# diode_sampling_gate_xformer.net
KiCad netlist of a schematic drawn in EAGLE
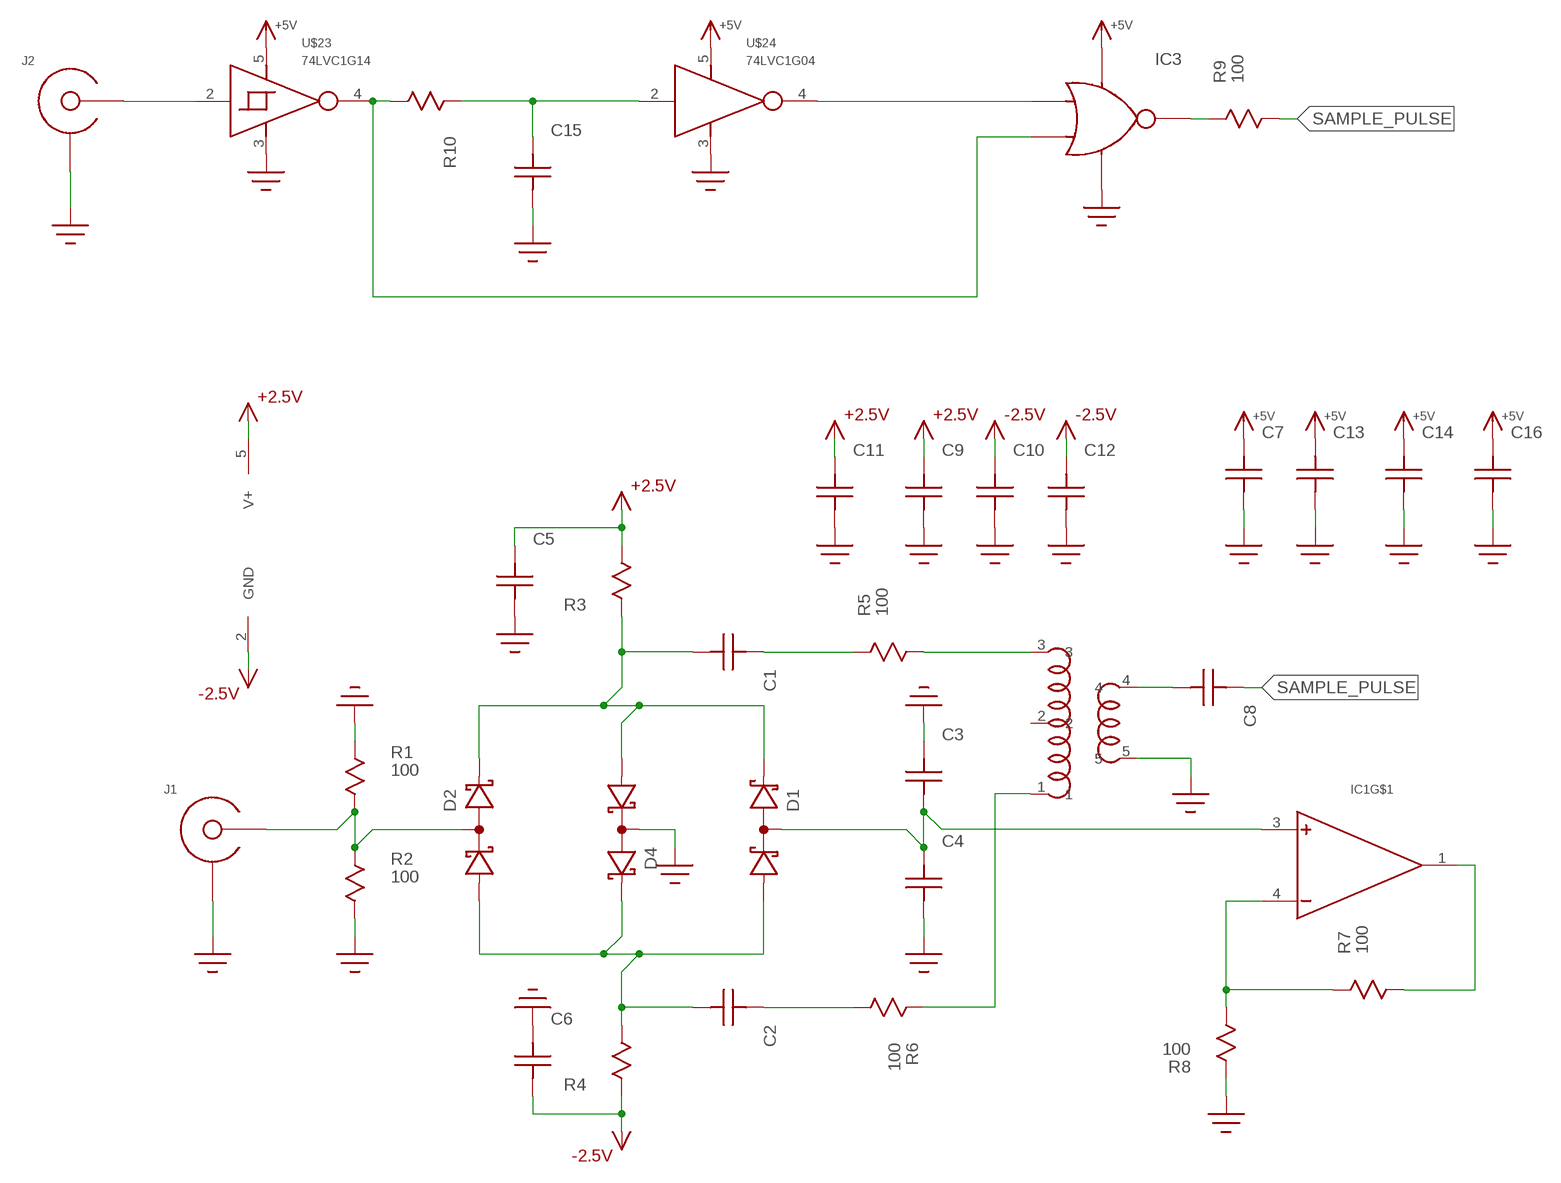
[diagram p0: schematic, sheet 1]

(export (version "E")
  (design (tool "Eeschema 10.0.6"))
  (components
    (comp (ref "C1")
      (value "C0603")
      (footprint "eagle-import:C0603")
      (libsource (lib "eagle-import") (part "C0603"))
    )
    (comp (ref "C2")
      (value "C0603")
      (footprint "eagle-import:C0603")
      (libsource (lib "eagle-import") (part "C0603"))
    )
    (comp (ref "C3")
      (value "C0603")
      (footprint "eagle-import:C0603")
      (libsource (lib "eagle-import") (part "C0603"))
    )
    (comp (ref "C4")
      (value "C0603")
      (footprint "eagle-import:C0603")
      (libsource (lib "eagle-import") (part "C0603"))
    )
    (comp (ref "C5")
      (value "C0603")
      (footprint "eagle-import:C0603")
      (libsource (lib "eagle-import") (part "C0603"))
    )
    (comp (ref "C6")
      (value "C0603")
      (footprint "eagle-import:C0603")
      (libsource (lib "eagle-import") (part "C0603"))
    )
    (comp (ref "C7")
      (value "C0603")
      (footprint "eagle-import:C0603")
      (libsource (lib "eagle-import") (part "C0603"))
    )
    (comp (ref "C8")
      (value "C0603")
      (footprint "eagle-import:C0603")
      (libsource (lib "eagle-import") (part "C0603"))
    )
    (comp (ref "C9")
      (value "C0603")
      (footprint "eagle-import:C0603")
      (libsource (lib "eagle-import") (part "C0603"))
    )
    (comp (ref "C10")
      (value "C0603")
      (footprint "eagle-import:C0603")
      (libsource (lib "eagle-import") (part "C0603"))
    )
    (comp (ref "C11")
      (value "C0805")
      (footprint "eagle-import:0805")
      (libsource (lib "eagle-import") (part "C0805"))
    )
    (comp (ref "C12")
      (value "C0805")
      (footprint "eagle-import:0805")
      (libsource (lib "eagle-import") (part "C0805"))
    )
    (comp (ref "C13")
      (value "C0603")
      (footprint "eagle-import:C0603")
      (libsource (lib "eagle-import") (part "C0603"))
    )
    (comp (ref "C14")
      (value "C0603")
      (footprint "eagle-import:C0603")
      (libsource (lib "eagle-import") (part "C0603"))
    )
    (comp (ref "C15")
      (value "C0603")
      (footprint "eagle-import:C0603")
      (libsource (lib "eagle-import") (part "C0603"))
    )
    (comp (ref "C16")
      (value "C0805")
      (footprint "eagle-import:0805")
      (libsource (lib "eagle-import") (part "C0805"))
    )
    (comp (ref "D1")
      (value "BAS40-04")
      (footprint "eagle-import:SOT-23")
      (libsource (lib "eagle-import") (part "BAS40-04"))
    )
    (comp (ref "D2")
      (value "BAS40-04")
      (footprint "eagle-import:SOT-23")
      (libsource (lib "eagle-import") (part "BAS40-04"))
    )
    (comp (ref "D4")
      (value "BAS40-04")
      (footprint "eagle-import:SOT-23")
      (libsource (lib "eagle-import") (part "BAS40-04"))
    )
    (comp (ref "IC1")
      (value "MCP6V81")
      (footprint "eagle-import:SOT23-5")
      (libsource (lib "eagle-import") (part "MCP6V81"))
    )
    (comp (ref "IC3")
      (value "74LVC1G02")
      (footprint "eagle-import:SOT23-5")
      (libsource (lib "eagle-import") (part "74LVC1G02"))
    )
    (comp (ref "J1")
      (value "EDGE_LAUNCH_JACK")
      (footprint "eagle-import:EDGE_LAUNCH_RF_CON")
      (libsource (lib "eagle-import") (part "EDGE_LAUNCH_JACK"))
    )
    (comp (ref "J2")
      (value "EDGE_LAUNCH_JACK")
      (footprint "eagle-import:EDGE_LAUNCH_RF_CON")
      (libsource (lib "eagle-import") (part "EDGE_LAUNCH_JACK"))
    )
    (comp (ref "R1")
      (value "100")
      (footprint "eagle-import:R0603")
      (libsource (lib "eagle-import") (part "R0603"))
    )
    (comp (ref "R2")
      (value "100")
      (footprint "eagle-import:R0603")
      (libsource (lib "eagle-import") (part "R0603"))
    )
    (comp (ref "R3")
      (value "R0603")
      (footprint "eagle-import:R0603")
      (libsource (lib "eagle-import") (part "R0603"))
    )
    (comp (ref "R4")
      (value "R0603")
      (footprint "eagle-import:R0603")
      (libsource (lib "eagle-import") (part "R0603"))
    )
    (comp (ref "R5")
      (value "100")
      (footprint "eagle-import:R0603")
      (libsource (lib "eagle-import") (part "R0603"))
    )
    (comp (ref "R6")
      (value "100")
      (footprint "eagle-import:R0603")
      (libsource (lib "eagle-import") (part "R0603"))
    )
    (comp (ref "R7")
      (value "100")
      (footprint "eagle-import:R0603")
      (libsource (lib "eagle-import") (part "R0603"))
    )
    (comp (ref "R8")
      (value "100")
      (footprint "eagle-import:R0603")
      (libsource (lib "eagle-import") (part "R0603"))
    )
    (comp (ref "R9")
      (value "100")
      (footprint "eagle-import:R0603")
      (libsource (lib "eagle-import") (part "R0603"))
    )
    (comp (ref "R10")
      (value "R0603")
      (footprint "eagle-import:R0603")
      (libsource (lib "eagle-import") (part "R0603"))
    )
    (comp (ref "T1")
      (value "MABAES0061")
      (footprint "eagle-import:MABAES0061")
      (libsource (lib "eagle-import") (part "MABAES0061"))
    )
    (comp (ref "U$23")
      (value "74LVC1G14")
      (footprint "eagle-import:SOT23-5")
      (libsource (lib "eagle-import") (part "74LVC1G14"))
    )
    (comp (ref "U$24")
      (value "74LVC1G04")
      (footprint "eagle-import:SOT23-5")
      (libsource (lib "eagle-import") (part "74LVC1G04"))
    )
  )
  (nets
    (net (code "1") (name "+2.5V") (class "Default")
      (node (ref "C11") (pin "P$2") (pinfunction "P$2_P$2") (pintype "bidirectional"))
      (node (ref "C5") (pin "P$2") (pinfunction "P$2_P$2") (pintype "bidirectional"))
      (node (ref "C9") (pin "P$2") (pinfunction "P$2_P$2") (pintype "bidirectional"))
      (node (ref "IC1") (pin "5") (pinfunction "V+_5") (pintype "bidirectional"))
      (node (ref "R3") (pin "P$2") (pinfunction "P$4_P$2") (pintype "bidirectional"))
    )
    (net (code "2") (name "+5V") (class "Default")
      (node (ref "C13") (pin "P$2") (pinfunction "P$2_P$2") (pintype "bidirectional"))
      (node (ref "C14") (pin "P$2") (pinfunction "P$2_P$2") (pintype "bidirectional"))
      (node (ref "C16") (pin "P$2") (pinfunction "P$2_P$2") (pintype "bidirectional"))
      (node (ref "C7") (pin "P$2") (pinfunction "P$2_P$2") (pintype "bidirectional"))
      (node (ref "IC3") (pin "5") (pinfunction "VCC_5") (pintype "bidirectional"))
      (node (ref "U$23") (pin "5") (pinfunction "VCC_5") (pintype "bidirectional"))
      (node (ref "U$24") (pin "5") (pinfunction "VCC_5") (pintype "bidirectional"))
    )
    (net (code "3") (name "-2.5V") (class "Default")
      (node (ref "C10") (pin "P$2") (pinfunction "P$2_P$2") (pintype "bidirectional"))
      (node (ref "C12") (pin "P$2") (pinfunction "P$2_P$2") (pintype "bidirectional"))
      (node (ref "C6") (pin "P$1") (pinfunction "P$1_P$1") (pintype "bidirectional"))
      (node (ref "IC1") (pin "2") (pinfunction "GND_2") (pintype "bidirectional"))
      (node (ref "R4") (pin "P$1") (pinfunction "P$3_P$1") (pintype "bidirectional"))
    )
    (net (code "4") (name "GND") (class "Default")
      (node (ref "C10") (pin "P$1") (pinfunction "P$1_P$1") (pintype "bidirectional"))
      (node (ref "C11") (pin "P$1") (pinfunction "P$1_P$1") (pintype "bidirectional"))
      (node (ref "C12") (pin "P$1") (pinfunction "P$1_P$1") (pintype "bidirectional"))
      (node (ref "C13") (pin "P$1") (pinfunction "P$1_P$1") (pintype "bidirectional"))
      (node (ref "C14") (pin "P$1") (pinfunction "P$1_P$1") (pintype "bidirectional"))
      (node (ref "C15") (pin "P$1") (pinfunction "P$1_P$1") (pintype "bidirectional"))
      (node (ref "C16") (pin "P$1") (pinfunction "P$1_P$1") (pintype "bidirectional"))
      (node (ref "C3") (pin "P$2") (pinfunction "P$2_P$2") (pintype "bidirectional"))
      (node (ref "C4") (pin "P$1") (pinfunction "P$1_P$1") (pintype "bidirectional"))
      (node (ref "C5") (pin "P$1") (pinfunction "P$1_P$1") (pintype "bidirectional"))
      (node (ref "C6") (pin "P$2") (pinfunction "P$2_P$2") (pintype "bidirectional"))
      (node (ref "C7") (pin "P$1") (pinfunction "P$1_P$1") (pintype "bidirectional"))
      (node (ref "C9") (pin "P$1") (pinfunction "P$1_P$1") (pintype "bidirectional"))
      (node (ref "D4") (pin "3") (pinfunction "COMMON_3") (pintype "bidirectional"))
      (node (ref "IC3") (pin "3") (pinfunction "GND_3") (pintype "bidirectional"))
      (node (ref "J1") (pin "GND@1") (pinfunction "SHIELD_GND@1") (pintype "bidirectional"))
      (node (ref "J1") (pin "GND@10") (pinfunction "SHIELD_GND@10") (pintype "bidirectional"))
      (node (ref "J1") (pin "GND@11") (pinfunction "SHIELD_GND@11") (pintype "bidirectional"))
      (node (ref "J1") (pin "GND@12") (pinfunction "SHIELD_GND@12") (pintype "bidirectional"))
      (node (ref "J1") (pin "GND@2") (pinfunction "SHIELD_GND@2") (pintype "bidirectional"))
      (node (ref "J1") (pin "GND@3") (pinfunction "SHIELD_GND@3") (pintype "bidirectional"))
      (node (ref "J1") (pin "GND@4") (pinfunction "SHIELD_GND@4") (pintype "bidirectional"))
      (node (ref "J1") (pin "GND@5") (pinfunction "SHIELD_GND@5") (pintype "bidirectional"))
      (node (ref "J1") (pin "GND@6") (pinfunction "SHIELD_GND@6") (pintype "bidirectional"))
      (node (ref "J1") (pin "GND@7") (pinfunction "SHIELD_GND@7") (pintype "bidirectional"))
      (node (ref "J1") (pin "GND@8") (pinfunction "SHIELD_GND@8") (pintype "bidirectional"))
      (node (ref "J1") (pin "GND@9") (pinfunction "SHIELD_GND@9") (pintype "bidirectional"))
      (node (ref "J1") (pin "SHIELD@1") (pinfunction "SHIELD_SHIELD@1") (pintype "bidirectional"))
      (node (ref "J1") (pin "SHIELD@2") (pinfunction "SHIELD_SHIELD@2") (pintype "bidirectional"))
      (node (ref "J2") (pin "GND@1") (pinfunction "SHIELD_GND@1") (pintype "bidirectional"))
      (node (ref "J2") (pin "GND@10") (pinfunction "SHIELD_GND@10") (pintype "bidirectional"))
      (node (ref "J2") (pin "GND@11") (pinfunction "SHIELD_GND@11") (pintype "bidirectional"))
      (node (ref "J2") (pin "GND@12") (pinfunction "SHIELD_GND@12") (pintype "bidirectional"))
      (node (ref "J2") (pin "GND@2") (pinfunction "SHIELD_GND@2") (pintype "bidirectional"))
      (node (ref "J2") (pin "GND@3") (pinfunction "SHIELD_GND@3") (pintype "bidirectional"))
      (node (ref "J2") (pin "GND@4") (pinfunction "SHIELD_GND@4") (pintype "bidirectional"))
      (node (ref "J2") (pin "GND@5") (pinfunction "SHIELD_GND@5") (pintype "bidirectional"))
      (node (ref "J2") (pin "GND@6") (pinfunction "SHIELD_GND@6") (pintype "bidirectional"))
      (node (ref "J2") (pin "GND@7") (pinfunction "SHIELD_GND@7") (pintype "bidirectional"))
      (node (ref "J2") (pin "GND@8") (pinfunction "SHIELD_GND@8") (pintype "bidirectional"))
      (node (ref "J2") (pin "GND@9") (pinfunction "SHIELD_GND@9") (pintype "bidirectional"))
      (node (ref "J2") (pin "SHIELD@1") (pinfunction "SHIELD_SHIELD@1") (pintype "bidirectional"))
      (node (ref "J2") (pin "SHIELD@2") (pinfunction "SHIELD_SHIELD@2") (pintype "bidirectional"))
      (node (ref "R1") (pin "P$1") (pinfunction "P$3_P$1") (pintype "bidirectional"))
      (node (ref "R2") (pin "P$2") (pinfunction "P$4_P$2") (pintype "bidirectional"))
      (node (ref "R8") (pin "P$1") (pinfunction "P$3_P$1") (pintype "bidirectional"))
      (node (ref "T1") (pin "5") (pinfunction "5_5") (pintype "bidirectional"))
      (node (ref "U$23") (pin "3") (pinfunction "GND_3") (pintype "bidirectional"))
      (node (ref "U$24") (pin "3") (pinfunction "GND_3") (pintype "bidirectional"))
    )
    (net (code "5") (name "Net-(C8-PadP$1)") (class "Default")
      (node (ref "C8") (pin "P$1") (pinfunction "P$1_P$1") (pintype "bidirectional"))
      (node (ref "T1") (pin "4") (pinfunction "4_4") (pintype "bidirectional"))
    )
    (net (code "6") (name "Net-(D1-ANODE)") (class "Default")
      (node (ref "C2") (pin "P$1") (pinfunction "P$1_P$1") (pintype "bidirectional"))
      (node (ref "D1") (pin "1") (pinfunction "ANODE_1") (pintype "bidirectional"))
      (node (ref "D2") (pin "1") (pinfunction "ANODE_1") (pintype "bidirectional"))
      (node (ref "D4") (pin "2") (pinfunction "CATHODE_2") (pintype "bidirectional"))
      (node (ref "R4") (pin "P$2") (pinfunction "P$4_P$2") (pintype "bidirectional"))
    )
    (net (code "7") (name "Net-(D1-CATHODE)") (class "Default")
      (node (ref "C1") (pin "P$1") (pinfunction "P$1_P$1") (pintype "bidirectional"))
      (node (ref "D1") (pin "2") (pinfunction "CATHODE_2") (pintype "bidirectional"))
      (node (ref "D2") (pin "2") (pinfunction "CATHODE_2") (pintype "bidirectional"))
      (node (ref "D4") (pin "1") (pinfunction "ANODE_1") (pintype "bidirectional"))
      (node (ref "R3") (pin "P$1") (pinfunction "P$3_P$1") (pintype "bidirectional"))
    )
    (net (code "8") (name "Net-(D1-COMMON)") (class "Default")
      (node (ref "C3") (pin "P$1") (pinfunction "P$1_P$1") (pintype "bidirectional"))
      (node (ref "C4") (pin "P$2") (pinfunction "P$2_P$2") (pintype "bidirectional"))
      (node (ref "D1") (pin "3") (pinfunction "COMMON_3") (pintype "bidirectional"))
      (node (ref "IC1") (pin "3") (pinfunction "+_3") (pintype "bidirectional"))
    )
    (net (code "9") (name "Net-(D2-COMMON)") (class "Default")
      (node (ref "D2") (pin "3") (pinfunction "COMMON_3") (pintype "bidirectional"))
      (node (ref "J1") (pin "CENTER") (pinfunction "CENTER_CENTER") (pintype "bidirectional"))
      (node (ref "R1") (pin "P$2") (pinfunction "P$4_P$2") (pintype "bidirectional"))
      (node (ref "R2") (pin "P$1") (pinfunction "P$3_P$1") (pintype "bidirectional"))
    )
    (net (code "10") (name "Net-(IC1A--)") (class "Default")
      (node (ref "IC1") (pin "4") (pinfunction "-_4") (pintype "bidirectional"))
      (node (ref "R7") (pin "P$1") (pinfunction "P$3_P$1") (pintype "bidirectional"))
      (node (ref "R8") (pin "P$2") (pinfunction "P$4_P$2") (pintype "bidirectional"))
    )
    (net (code "11") (name "Net-(IC1A-OUT)") (class "Default")
      (node (ref "IC1") (pin "1") (pinfunction "OUT_1") (pintype "bidirectional"))
      (node (ref "R7") (pin "P$2") (pinfunction "P$4_P$2") (pintype "bidirectional"))
    )
    (net (code "12") (name "Net-(IC3-A)") (class "Default")
      (node (ref "IC3") (pin "1") (pinfunction "A_1") (pintype "bidirectional"))
      (node (ref "U$24") (pin "4") (pinfunction "OUT_4") (pintype "bidirectional"))
    )
    (net (code "13") (name "Net-(IC3-B)") (class "Default")
      (node (ref "IC3") (pin "2") (pinfunction "B_2") (pintype "bidirectional"))
      (node (ref "R10") (pin "P$2") (pinfunction "P$4_P$2") (pintype "bidirectional"))
      (node (ref "U$23") (pin "4") (pinfunction "OUT_4") (pintype "bidirectional"))
    )
    (net (code "14") (name "Net-(IC3-Y)") (class "Default")
      (node (ref "IC3") (pin "4") (pinfunction "Y_4") (pintype "bidirectional"))
      (node (ref "R9") (pin "P$1") (pinfunction "P$3_P$1") (pintype "bidirectional"))
    )
    (net (code "15") (name "Net-(R5-P$3)") (class "Default")
      (node (ref "C1") (pin "P$2") (pinfunction "P$2_P$2") (pintype "bidirectional"))
      (node (ref "R5") (pin "P$1") (pinfunction "P$3_P$1") (pintype "bidirectional"))
    )
    (net (code "16") (name "Net-(R5-P$4)") (class "Default")
      (node (ref "R5") (pin "P$2") (pinfunction "P$4_P$2") (pintype "bidirectional"))
      (node (ref "T1") (pin "3") (pinfunction "3_3") (pintype "bidirectional"))
    )
    (net (code "17") (name "Net-(R6-P$3)") (class "Default")
      (node (ref "R6") (pin "P$1") (pinfunction "P$3_P$1") (pintype "bidirectional"))
      (node (ref "T1") (pin "1") (pinfunction "1_1") (pintype "bidirectional"))
    )
    (net (code "18") (name "Net-(R6-P$4)") (class "Default")
      (node (ref "C2") (pin "P$2") (pinfunction "P$2_P$2") (pintype "bidirectional"))
      (node (ref "R6") (pin "P$2") (pinfunction "P$4_P$2") (pintype "bidirectional"))
    )
    (net (code "19") (name "Net-(R10-P$3)") (class "Default")
      (node (ref "C15") (pin "P$2") (pinfunction "P$2_P$2") (pintype "bidirectional"))
      (node (ref "R10") (pin "P$1") (pinfunction "P$3_P$1") (pintype "bidirectional"))
      (node (ref "U$24") (pin "2") (pinfunction "IN_2") (pintype "bidirectional"))
    )
    (net (code "20") (name "Net-(U$23-IN)") (class "Default")
      (node (ref "J2") (pin "CENTER") (pinfunction "CENTER_CENTER") (pintype "bidirectional"))
      (node (ref "U$23") (pin "2") (pinfunction "IN_2") (pintype "bidirectional"))
    )
    (net (code "21") (name "SAMPLE_PULSE") (class "Default")
      (node (ref "C8") (pin "P$2") (pinfunction "P$2_P$2") (pintype "bidirectional"))
      (node (ref "R9") (pin "P$2") (pinfunction "P$4_P$2") (pintype "bidirectional"))
    )
    (net (code "22") (name "unconnected-(T1-Pad2)") (class "Default")
      (node (ref "T1") (pin "2") (pinfunction "2_2") (pintype "bidirectional"))
    )
  )
)
